# SCH_Wojcik.net
KiCad netlist of a schematic drawn in Altium Designer
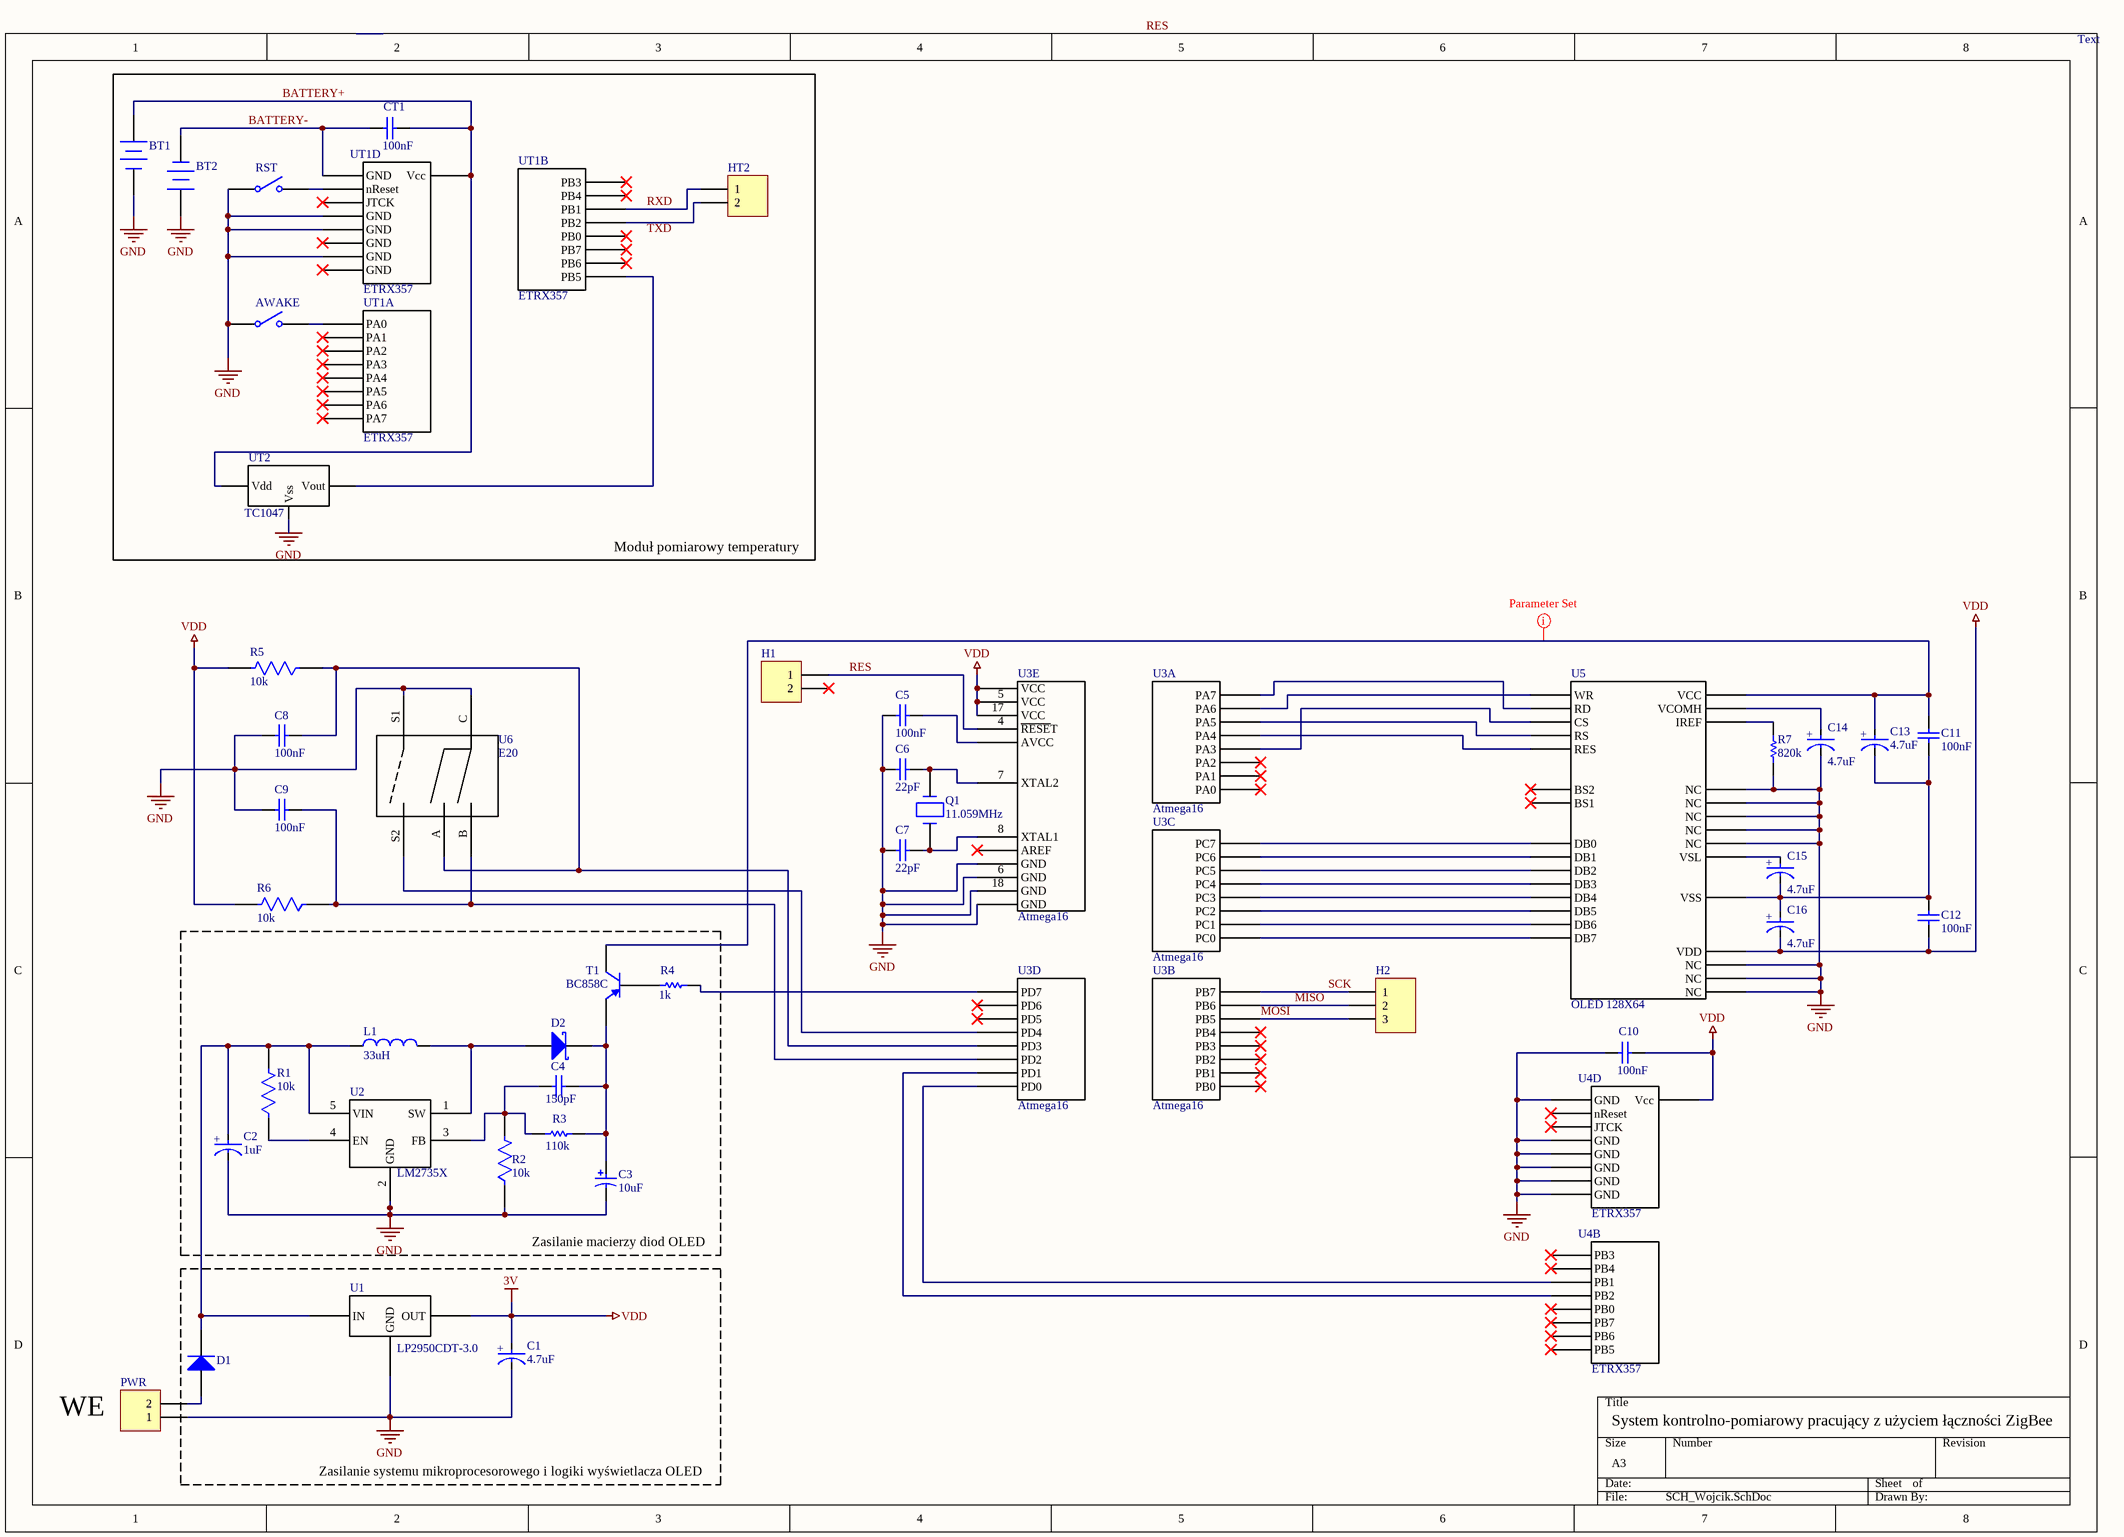
[diagram p0: SCH_Wojcik.SchDoc]

(export (version "E")
  (design (tool "Eeschema 10.0.6"))
  (components
    (comp (ref "AWAKE")
      (value "~")
      (footprint "SPST-2")
      (description "Single-Pole, Single-Throw Switch")
      (fields (field (name "PUBLISHER") "Altium Limited"))
      (libsource (lib "Miscellaneous Devices") (part "SW-SPST"))
    )
    (comp (ref "BT1")
      (value "Battery")
      (footprint "BAT-2")
      (description "Multicell Battery")
      (fields (field (name "PUBLISHER") "Altium Limited"))
      (libsource (lib "Miscellaneous Devices") (part "Battery"))
    )
    (comp (ref "BT2")
      (value "Battery")
      (footprint "BAT-2")
      (description "Multicell Battery")
      (fields (field (name "PUBLISHER") "Altium Limited"))
      (libsource (lib "Miscellaneous Devices") (part "Battery"))
    )
    (comp (ref "C1")
      (value "4.7uF")
      (footprint "FP-TAJB-MFG")
      (description "CAP TANT 4.7UF 10% 10V 1411")
      (fields
        (field (name "MANUFACTURER") "AVX Corporation")
        (field (name "MANUFACTURER PART NUMBER") "TAJB475K010RNJ")
      )
      (libsource (lib "Schlib_Wojcik_Jagienka") (part "cap4.7u"))
    )
    (comp (ref "C2")
      (value "1uF")
      (footprint "FP-TAJB-MFG")
      (description "CAP TANT 1UF 10% 35V 1411")
      (fields (field (name "TOLERANCE") "10%") (field (name "VOLTAGE") "35V"))
      (libsource (lib "Schlib_Wojcik_Jagienka") (part "1uF"))
    )
    (comp (ref "C3")
      (value "10uF")
      (footprint "CAPMP3529X21-T_V")
      (description "Standard Tantalum, 10 uF, +/- 20%, 20 V, -55 to 125 degC, 2-Pin SMD, RoHS, Tape and Reel")
      (fields (field (name "VOLTAGE") "20VDC") (field (name "MANUFACTURER") "AVX"))
      (libsource (lib "Schlib_Wojcik_Jagienka") (part "10uF"))
    )
    (comp (ref "C4")
      (value "150pF")
      (footprint "CAPC1608X90X35LL15T15")
      (fields (field (name "MANUFACTURER") "Kemet") (field (name "PART NUMBER") "C0603C151J5GAC7867"))
      (libsource (lib "Schlib_Wojcik_Jagienka") (part "150pF"))
    )
    (comp (ref "C5")
      (value "100nF")
      (footprint "CAPC1608X90X35LL10T15")
      (description "Chip Capacitor, 0.1 uF, +/- 10%, 50 V, -55 to 125 degC, 0603 (1608 Metric), RoHS, Tape and Reel")
      (fields (field (name "TOLERANCE") "10%") (field (name "VOLTAGE") "50V"))
      (libsource (lib "Schlib_Wojcik_Jagienka") (part "cap100n"))
    )
    (comp (ref "C6")
      (value "22pF")
      (footprint "CAPC1005X56X25LL10T15")
      (fields
        (field (name "PART NUMBER") "04025A220JAT2A")
        (field (name "MANUFACTURER") "AVX Interconnect / Elco")
      )
      (libsource (lib "Schlib_Wojcik_Jagienka") (part "22pF"))
    )
    (comp (ref "C7")
      (value "22pF")
      (footprint "CAPC1005X56X25LL10T15")
      (fields
        (field (name "PART NUMBER") "04025A220JAT2A")
        (field (name "MANUFACTURER") "AVX Interconnect / Elco")
      )
      (libsource (lib "Schlib_Wojcik_Jagienka") (part "22pF"))
    )
    (comp (ref "C8")
      (value "100nF")
      (footprint "CAPC1608X90X35LL10T15")
      (description "Chip Capacitor, 0.1 uF, +/- 10%, 50 V, -55 to 125 degC, 0603 (1608 Metric), RoHS, Tape and Reel")
      (fields (field (name "TOLERANCE") "10%") (field (name "VOLTAGE") "50V"))
      (libsource (lib "Schlib_Wojcik_Jagienka") (part "cap100n"))
    )
    (comp (ref "C9")
      (value "100nF")
      (footprint "CAPC1608X90X35LL10T15")
      (description "Chip Capacitor, 0.1 uF, +/- 10%, 50 V, -55 to 125 degC, 0603 (1608 Metric), RoHS, Tape and Reel")
      (fields (field (name "TOLERANCE") "10%") (field (name "VOLTAGE") "50V"))
      (libsource (lib "Schlib_Wojcik_Jagienka") (part "cap100n"))
    )
    (comp (ref "C10")
      (value "100nF")
      (footprint "CAPC1608X90X35LL10T15")
      (description "Chip Capacitor, 0.1 uF, +/- 10%, 50 V, -55 to 125 degC, 0603 (1608 Metric), RoHS, Tape and Reel")
      (fields (field (name "TOLERANCE") "10%") (field (name "VOLTAGE") "50V"))
      (libsource (lib "Schlib_Wojcik_Jagienka") (part "cap100n"))
    )
    (comp (ref "C11")
      (value "100nF")
      (footprint "CAPC1608X90X35LL10T15")
      (description "Chip Capacitor, 0.1 uF, +/- 10%, 50 V, -55 to 125 degC, 0603 (1608 Metric), RoHS, Tape and Reel")
      (fields (field (name "TOLERANCE") "10%") (field (name "VOLTAGE") "50V"))
      (libsource (lib "Schlib_Wojcik_Jagienka") (part "cap100n"))
    )
    (comp (ref "C12")
      (value "100nF")
      (footprint "CAPC1608X90X35LL10T15")
      (description "Chip Capacitor, 0.1 uF, +/- 10%, 50 V, -55 to 125 degC, 0603 (1608 Metric), RoHS, Tape and Reel")
      (fields (field (name "TOLERANCE") "10%") (field (name "VOLTAGE") "50V"))
      (libsource (lib "Schlib_Wojcik_Jagienka") (part "cap100n"))
    )
    (comp (ref "C13")
      (value "4.7uF")
      (footprint "FP-TAJB-MFG")
      (description "CAP TANT 4.7UF 10% 10V 1411")
      (fields
        (field (name "MANUFACTURER") "AVX Corporation")
        (field (name "MANUFACTURER PART NUMBER") "TAJB475K010RNJ")
      )
      (libsource (lib "Schlib_Wojcik_Jagienka") (part "cap4.7u"))
    )
    (comp (ref "C14")
      (value "4.7uF")
      (footprint "FP-TAJB-MFG")
      (description "CAP TANT 4.7UF 10% 10V 1411")
      (fields
        (field (name "MANUFACTURER") "AVX Corporation")
        (field (name "MANUFACTURER PART NUMBER") "TAJB475K010RNJ")
      )
      (libsource (lib "Schlib_Wojcik_Jagienka") (part "cap4.7u"))
    )
    (comp (ref "C15")
      (value "4.7uF")
      (footprint "FP-TAJB-MFG")
      (description "CAP TANT 4.7UF 10% 10V 1411")
      (fields
        (field (name "MANUFACTURER") "AVX Corporation")
        (field (name "MANUFACTURER PART NUMBER") "TAJB475K010RNJ")
      )
      (libsource (lib "Schlib_Wojcik_Jagienka") (part "cap4.7u"))
    )
    (comp (ref "C16")
      (value "4.7uF")
      (footprint "FP-TAJB-MFG")
      (description "CAP TANT 4.7UF 10% 10V 1411")
      (fields
        (field (name "MANUFACTURER") "AVX Corporation")
        (field (name "MANUFACTURER PART NUMBER") "TAJB475K010RNJ")
      )
      (libsource (lib "Schlib_Wojcik_Jagienka") (part "cap4.7u"))
    )
    (comp (ref "CT1")
      (value "100nF")
      (footprint "CAPC1608X90X35LL10T15")
      (description "Chip Capacitor, 0.1 uF, +/- 10%, 50 V, -55 to 125 degC, 0603 (1608 Metric), RoHS, Tape and Reel")
      (fields (field (name "TOLERANCE") "10%") (field (name "VOLTAGE") "50V"))
      (libsource (lib "Schlib_Wojcik_Jagienka") (part "cap100n"))
    )
    (comp (ref "D1")
      (value "Diode 1N5407")
      (footprint "DO-201AD")
      (description "3 Amp Medium Power Silicon Rectifier Diode")
      (fields (field (name "PUBLISHER") "Altium Limited"))
      (libsource (lib "Miscellaneous Devices") (part "Diode 1N5407"))
    )
    (comp (ref "D2")
      (value "D Schottky")
      (footprint "SMB")
      (description "Schottky Diode")
      (fields (field (name "PUBLISHER") "Altium Limited"))
      (libsource (lib "Miscellaneous Devices") (part "D Schottky"))
    )
    (comp (ref "H1")
      (value "Header 2")
      (footprint "HDR1X2")
      (description "Header, 2-Pin")
      (fields (field (name "PUBLISHER") "Altium Limited"))
      (libsource (lib "Miscellaneous Connectors") (part "Header 2"))
    )
    (comp (ref "H2")
      (value "Header 3")
      (footprint "HDR1X3")
      (description "Header, 3-Pin")
      (fields (field (name "PUBLISHER") "Altium Limited"))
      (libsource (lib "Miscellaneous Connectors") (part "Header 3"))
    )
    (comp (ref "HT2")
      (value "Header 2")
      (footprint "HDR1X2")
      (description "Header, 2-Pin")
      (fields (field (name "PUBLISHER") "Altium Limited"))
      (libsource (lib "") (part "Header 2_2"))
    )
    (comp (ref "L1")
      (value "33uH")
      (footprint "WE-PD4-L")
      (description "SMD-Power Inductor WE-PD4, L = 33.0 µH")
      (libsource (lib "Schlib_Wojcik_Jagienka") (part "CMP-0227-00804-1"))
    )
    (comp (ref "PWR")
      (value "Header 2")
      (footprint "HDR1X2")
      (description "Header, 2-Pin")
      (fields (field (name "PUBLISHER") "Altium Limited"))
      (libsource (lib "") (part "Header 2_1"))
    )
    (comp (ref "Q1")
      (value "11.059MHz")
      (footprint "XTAL_ABLS2-11.059MHZ-B4Y-T")
      (description "11.059MHz Â±30ppm Crystal 18pF 50 Ohms HC-49/US")
      (fields (field (name "DIGI-KEY_PART_NUMBER") "ABLS2-11.059MHZ-B4Y-T-ND") (field (name "MF") "Abracon"))
      (libsource (lib "ABLS2-11.059MHZ-B4Y-T") (part "ABLS2-11.059MHZ-B4Y-T"))
    )
    (comp (ref "R1")
      (value "10k")
      (footprint "FP-CRCW0402-e3-IPC_A")
      (description "RES SMD 10K OHM 1% 1/16W 0402")
      (fields (field (name "TOLERANCE") "1%"))
      (libsource (lib "Schlib_Wojcik_Jagienka") (part "10k"))
    )
    (comp (ref "R2")
      (value "10k")
      (footprint "FP-CRCW0402-e3-IPC_A")
      (description "RES SMD 10K OHM 1% 1/16W 0402")
      (fields (field (name "TOLERANCE") "1%"))
      (libsource (lib "Schlib_Wojcik_Jagienka") (part "10k"))
    )
    (comp (ref "R3")
      (value "110k")
      (footprint "RESC1005X40X25LL05T05")
      (fields (field (name "MANUFACTURER") "Vishay Dale") (field (name "PART NUMBER") "CRCW0402110KFKED"))
      (libsource (lib "Schlib_Wojcik_Jagienka") (part "110k"))
    )
    (comp (ref "R4")
      (value "1k")
      (footprint "RESC2013X50X30LL20T20")
      (fields (field (name "PART NUMBER") "CRCW08051K00FKEA") (field (name "MANUFACTURER") "Vishay Dale"))
      (libsource (lib "Schlib_Wojcik_Jagienka") (part "1k"))
    )
    (comp (ref "R5")
      (value "10k")
      (footprint "FP-CRCW0402-e3-IPC_A")
      (description "RES SMD 10K OHM 1% 1/16W 0402")
      (fields (field (name "TOLERANCE") "1%"))
      (libsource (lib "Schlib_Wojcik_Jagienka") (part "10k"))
    )
    (comp (ref "R6")
      (value "10k")
      (footprint "FP-CRCW0402-e3-IPC_A")
      (description "RES SMD 10K OHM 1% 1/16W 0402")
      (fields (field (name "TOLERANCE") "1%"))
      (libsource (lib "Schlib_Wojcik_Jagienka") (part "10k"))
    )
    (comp (ref "R7")
      (value "820k")
      (footprint "RESC1005X40X25NL05T05")
      (fields (field (name "PART NUMBER") "CRCW0402820KFKED") (field (name "MANUFACTURER") "Vishay Dale"))
      (libsource (lib "Schlib_Wojcik_Jagienka") (part "820k"))
    )
    (comp (ref "RST")
      (value "~")
      (footprint "SPST-2")
      (description "Single-Pole, Single-Throw Switch")
      (fields (field (name "PUBLISHER") "Altium Limited"))
      (libsource (lib "Miscellaneous Devices") (part "SW-SPST"))
    )
    (comp (ref "T1")
      (value "BC858C")
      (footprint "INF-SOT23_L")
      (description "PNP Silicon AF Transistor, 30 V VCEO, 100 mA IC, SOT23, Reel, Green")
      (fields (field (name "MANUFACTURER") "Infineon"))
      (libsource (lib "Schlib_Wojcik_Jagienka") (part "CMP-1177-00041-1"))
    )
    (comp (ref "U1")
      (value "LP2950CDT-3.0")
      (footprint "ON_Semi_369C_0")
      (libsource (lib "Schlib_Wojcik_Jagienka") (part "LP2950CDT-3.0"))
    )
    (comp (ref "U2")
      (value "LM2735X")
      (footprint "SOT95P280X145-5N")
      (libsource (lib "Schlib_Wojcik_Jagienka") (part "LM2735X"))
    )
    (comp (ref "U3") (value "Atmega16") (footprint "44A_L") (libsource (lib "") (part "Atmega16_4")))
    (comp (ref "U4") (value "ETRX357") (footprint "ETRX357") (libsource (lib "") (part "ETRX357_3")))
    (comp (ref "U5") (value "OLED 128X64") (libsource (lib "Schlib_Wojcik_Jagienka") (part "OLED")))
    (comp (ref "U6")
      (value "E20")
      (footprint "Encoder")
      (libsource (lib "Schlib_Wojcik_Jagienka") (part "E20"))
    )
    (comp (ref "UT1") (value "ETRX357") (footprint "ETRX357") (libsource (lib "") (part "ETRX357_4")))
    (comp (ref "UT2")
      (value "TC1047")
      (footprint "SOT-23")
      (libsource (lib "Schlib_Wojcik_Jagienka") (part "TC1047"))
    )
  )
  (nets
    (net (code "1") (name "/BATTERY+") (class "Default")
      (node (ref "BT1") (pin "1") (pinfunction "+_1") (pintype "passive"))
      (node (ref "CT1") (pin "2") (pinfunction "2_2") (pintype "passive"))
      (node (ref "UT1") (pin "32") (pinfunction "Vcc_32") (pintype "passive"))
      (node (ref "UT2") (pin "1") (pinfunction "Vdd_1") (pintype "passive"))
    )
    (net (code "2") (name "/BATTERY-") (class "Default")
      (node (ref "BT2") (pin "2") (pinfunction "-_2") (pintype "passive"))
      (node (ref "CT1") (pin "1") (pinfunction "1_1") (pintype "passive"))
      (node (ref "UT1") (pin "1") (pinfunction "GND_1") (pintype "passive"))
    )
    (net (code "3") (name "/MISO") (class "Default")
      (node (ref "H2") (pin "2") (pinfunction "2_2") (pintype "passive"))
      (node (ref "U3") (pin "2") (pinfunction "PB6_2") (pintype "passive"))
    )
    (net (code "4") (name "/MOSI") (class "Default")
      (node (ref "H2") (pin "3") (pinfunction "3_3") (pintype "passive"))
      (node (ref "U3") (pin "1") (pinfunction "PB5_1") (pintype "passive"))
    )
    (net (code "5") (name "/RES") (class "Default")
      (node (ref "H1") (pin "1") (pinfunction "1_1") (pintype "passive"))
      (node (ref "U3") (pin "4") (pinfunction "~{RESE}T_4") (pintype "passive"))
    )
    (net (code "6") (name "/RXD") (class "Default")
      (node (ref "HT2") (pin "1") (pinfunction "1_1") (pintype "passive"))
      (node (ref "UT1") (pin "17") (pinfunction "PB1_17") (pintype "passive"))
    )
    (net (code "7") (name "/SCK") (class "Default")
      (node (ref "H2") (pin "1") (pinfunction "1_1") (pintype "passive"))
      (node (ref "U3") (pin "3") (pinfunction "PB7_3") (pintype "passive"))
    )
    (net (code "9") (name "3V") (class "Default")
      (node (ref "C1") (pin "2") (pinfunction "A_2") (pintype "passive"))
      (node (ref "C10") (pin "2") (pinfunction "2_2") (pintype "passive"))
      (node (ref "C12") (pin "1") (pinfunction "1_1") (pintype "passive"))
      (node (ref "C16") (pin "1") (pinfunction "C_1") (pintype "passive"))
      (node (ref "R5") (pin "2") (pinfunction "2_2") (pintype "passive"))
      (node (ref "R6") (pin "2") (pinfunction "2_2") (pintype "passive"))
      (node (ref "U1") (pin "3") (pinfunction "OUT_3") (pintype "passive"))
      (node (ref "U3") (pin "17") (pinfunction "VCC_17") (pintype "passive"))
      (node (ref "U3") (pin "38") (pinfunction "VCC_38") (pintype "passive"))
      (node (ref "U3") (pin "5") (pinfunction "VCC_5") (pintype "passive"))
      (node (ref "U4") (pin "32") (pinfunction "Vcc_32") (pintype "passive"))
      (node (ref "U5") (pin "21") (pinfunction "VDD_21") (pintype "passive"))
    )
    (net (code "10") (name "GND") (class "Default")
      (node (ref "AWAKE") (pin "1") (pinfunction "COMMON_1") (pintype "passive"))
      (node (ref "BT1") (pin "2") (pinfunction "-_2") (pintype "passive"))
      (node (ref "BT2") (pin "1") (pinfunction "+_1") (pintype "passive"))
      (node (ref "C1") (pin "1") (pinfunction "C_1") (pintype "passive"))
      (node (ref "C10") (pin "1") (pinfunction "1_1") (pintype "passive"))
      (node (ref "C14") (pin "1") (pinfunction "C_1") (pintype "passive"))
      (node (ref "C2") (pin "1") (pinfunction "C_1") (pintype "passive"))
      (node (ref "C3") (pin "2") (pinfunction "2_2") (pintype "passive"))
      (node (ref "C5") (pin "1") (pinfunction "1_1") (pintype "passive"))
      (node (ref "C6") (pin "1") (pinfunction "1_1") (pintype "passive"))
      (node (ref "C7") (pin "1") (pinfunction "1_1") (pintype "passive"))
      (node (ref "C8") (pin "1") (pinfunction "1_1") (pintype "passive"))
      (node (ref "C9") (pin "1") (pinfunction "1_1") (pintype "passive"))
      (node (ref "PWR") (pin "1") (pinfunction "1_1") (pintype "passive"))
      (node (ref "R2") (pin "1") (pinfunction "1_1") (pintype "passive"))
      (node (ref "R7") (pin "1") (pinfunction "1_1") (pintype "passive"))
      (node (ref "RST") (pin "1") (pinfunction "COMMON_1") (pintype "passive"))
      (node (ref "U1") (pin "2") (pinfunction "GND_2") (pintype "passive"))
      (node (ref "U2") (pin "2") (pinfunction "GND_2") (pintype "passive"))
      (node (ref "U3") (pin "18") (pinfunction "GND_18") (pintype "passive"))
      (node (ref "U3") (pin "28") (pinfunction "GND_28") (pintype "passive"))
      (node (ref "U3") (pin "39") (pinfunction "GND_39") (pintype "passive"))
      (node (ref "U3") (pin "6") (pinfunction "GND_6") (pintype "passive"))
      (node (ref "U4") (pin "1") (pinfunction "GND_1") (pintype "passive"))
      (node (ref "U4") (pin "13") (pinfunction "GND_13") (pintype "passive"))
      (node (ref "U4") (pin "19") (pinfunction "GND_19") (pintype "passive"))
      (node (ref "U4") (pin "20") (pinfunction "GND_20") (pintype "passive"))
      (node (ref "U4") (pin "31") (pinfunction "GND_31") (pintype "passive"))
      (node (ref "U4") (pin "33") (pinfunction "GND_33") (pintype "passive"))
      (node (ref "U5") (pin "18") (pinfunction "NC_18") (pintype "passive"))
      (node (ref "U5") (pin "22") (pinfunction "NC_22") (pintype "passive"))
      (node (ref "U5") (pin "23") (pinfunction "NC_23") (pintype "passive"))
      (node (ref "U5") (pin "24") (pinfunction "NC_24") (pintype "passive"))
      (node (ref "U5") (pin "25") (pinfunction "NC_25") (pintype "passive"))
      (node (ref "U5") (pin "26") (pinfunction "NC_26") (pintype "passive"))
      (node (ref "U5") (pin "27") (pinfunction "NC_27") (pintype "passive"))
      (node (ref "U5") (pin "28") (pinfunction "NC_28") (pintype "passive"))
      (node (ref "U6") (pin "C") (pintype "passive"))
      (node (ref "U6") (pin "S1") (pintype "passive"))
      (node (ref "UT1") (pin "13") (pinfunction "GND_13") (pintype "passive"))
      (node (ref "UT1") (pin "20") (pinfunction "GND_20") (pintype "passive"))
      (node (ref "UT1") (pin "33") (pinfunction "GND_33") (pintype "passive"))
      (node (ref "UT2") (pin "3") (pinfunction "Vss_3") (pintype "passive"))
    )
    (net (code "11") (name "Net-(AWAKE-NO)") (class "Default")
      (node (ref "AWAKE") (pin "2") (pinfunction "NO_2") (pintype "passive"))
      (node (ref "UT1") (pin "9") (pinfunction "PA0_9") (pintype "passive"))
    )
    (net (code "12") (name "Net-(C2-A)") (class "Default")
      (node (ref "C2") (pin "2") (pinfunction "A_2") (pintype "passive"))
      (node (ref "D1") (pin "2") (pinfunction "K_2") (pintype "passive"))
      (node (ref "L1") (pin "1") (pinfunction "1_1") (pintype "passive"))
      (node (ref "R1") (pin "2") (pinfunction "2_2") (pintype "passive"))
      (node (ref "U1") (pin "1") (pinfunction "IN_1") (pintype "passive"))
      (node (ref "U2") (pin "5") (pinfunction "VIN_5") (pintype "passive"))
    )
    (net (code "13") (name "Net-(C13-A)") (class "Default")
      (node (ref "C11") (pin "2") (pinfunction "2_2") (pintype "passive"))
      (node (ref "C13") (pin "2") (pinfunction "A_2") (pintype "passive"))
      (node (ref "T1") (pin "3") (pinfunction "C_3") (pintype "passive"))
      (node (ref "U5") (pin "2") (pinfunction "VCC_2") (pintype "passive"))
    )
    (net (code "14") (name "Net-(C13-C)") (class "Default")
      (node (ref "C11") (pin "1") (pinfunction "1_1") (pintype "passive"))
      (node (ref "C12") (pin "2") (pinfunction "2_2") (pintype "passive"))
      (node (ref "C13") (pin "1") (pinfunction "C_1") (pintype "passive"))
      (node (ref "C15") (pin "1") (pinfunction "C_1") (pintype "passive"))
      (node (ref "C16") (pin "2") (pinfunction "A_2") (pintype "passive"))
      (node (ref "U5") (pin "29") (pinfunction "VSS_29") (pintype "passive"))
    )
    (net (code "15") (name "Net-(C14-A)") (class "Default")
      (node (ref "C14") (pin "2") (pinfunction "A_2") (pintype "passive"))
      (node (ref "U5") (pin "3") (pinfunction "VCOMH_3") (pintype "passive"))
    )
    (net (code "16") (name "Net-(C15-A)") (class "Default")
      (node (ref "C15") (pin "2") (pinfunction "A_2") (pintype "passive"))
      (node (ref "U5") (pin "30") (pinfunction "VSL_30") (pintype "passive"))
    )
    (net (code "17") (name "Net-(D1-A)") (class "Default")
      (node (ref "D1") (pin "1") (pinfunction "A_1") (pintype "passive"))
      (node (ref "PWR") (pin "2") (pinfunction "2_2") (pintype "passive"))
    )
    (net (code "18") (name "Net-(D2-A)") (class "Default")
      (node (ref "D2") (pin "1") (pinfunction "A_1") (pintype "passive"))
      (node (ref "L1") (pin "2") (pinfunction "2_2") (pintype "passive"))
      (node (ref "U2") (pin "1") (pinfunction "SW_1") (pintype "passive"))
    )
    (net (code "19") (name "Net-(D2-K)") (class "Default")
      (node (ref "C3") (pin "1") (pinfunction "1_1") (pintype "passive"))
      (node (ref "C4") (pin "2") (pinfunction "2_2") (pintype "passive"))
      (node (ref "D2") (pin "2") (pinfunction "K_2") (pintype "passive"))
      (node (ref "R3") (pin "2") (pinfunction "2_2") (pintype "passive"))
      (node (ref "T1") (pin "2") (pinfunction "E_2") (pintype "passive"))
    )
    (net (code "20") (name "Net-(RST-NO)") (class "Default")
      (node (ref "RST") (pin "2") (pinfunction "NO_2") (pintype "passive"))
      (node (ref "UT1") (pin "7") (pinfunction "nReset_7") (pintype "passive"))
    )
    (net (code "21") (name "Net-(T1-B)") (class "Default")
      (node (ref "R4") (pin "1") (pinfunction "1_1") (pintype "passive"))
      (node (ref "T1") (pin "1") (pinfunction "B_1") (pintype "passive"))
    )
    (net (code "22") (name "Net-(U2-EN)") (class "Default")
      (node (ref "R1") (pin "1") (pinfunction "1_1") (pintype "passive"))
      (node (ref "U2") (pin "4") (pinfunction "EN_4") (pintype "passive"))
    )
    (net (code "23") (name "Net-(U2-FB)") (class "Default")
      (node (ref "C4") (pin "1") (pinfunction "1_1") (pintype "passive"))
      (node (ref "R2") (pin "2") (pinfunction "2_2") (pintype "passive"))
      (node (ref "R3") (pin "1") (pinfunction "1_1") (pintype "passive"))
      (node (ref "U2") (pin "3") (pinfunction "FB_3") (pintype "passive"))
    )
    (net (code "24") (name "Net-(U3A-PA3)") (class "Default")
      (node (ref "U3") (pin "34") (pinfunction "PA3_34") (pintype "passive"))
      (node (ref "U5") (pin "15") (pinfunction "CS_15") (pintype "passive"))
    )
    (net (code "25") (name "Net-(U3A-PA4)") (class "Default")
      (node (ref "U3") (pin "33") (pinfunction "PA4_33") (pintype "passive"))
      (node (ref "U5") (pin "26") (pinfunction "RES_26") (pintype "passive"))
    )
    (net (code "26") (name "Net-(U3A-PA5)") (class "Default")
      (node (ref "U3") (pin "32") (pinfunction "PA5_32") (pintype "passive"))
      (node (ref "U5") (pin "17") (pinfunction "RS_17") (pintype "passive"))
    )
    (net (code "27") (name "Net-(U3A-PA6)") (class "Default")
      (node (ref "U3") (pin "31") (pinfunction "PA6_31") (pintype "passive"))
      (node (ref "U5") (pin "14") (pinfunction "WR_14") (pintype "passive"))
    )
    (net (code "28") (name "Net-(U3A-PA7)") (class "Default")
      (node (ref "U3") (pin "30") (pinfunction "PA7_30") (pintype "passive"))
      (node (ref "U5") (pin "13") (pinfunction "RD_13") (pintype "passive"))
    )
    (net (code "29") (name "Net-(U3C-PC0)") (class "Default")
      (node (ref "U3") (pin "19") (pinfunction "PC0_19") (pintype "passive"))
      (node (ref "U5") (pin "5") (pinfunction "DB7_5") (pintype "passive"))
    )
    (net (code "30") (name "Net-(U3C-PC1)") (class "Default")
      (node (ref "U3") (pin "20") (pinfunction "PC1_20") (pintype "passive"))
      (node (ref "U5") (pin "6") (pinfunction "DB6_6") (pintype "passive"))
    )
    (net (code "31") (name "Net-(U3C-PC2)") (class "Default")
      (node (ref "U3") (pin "21") (pinfunction "PC2_21") (pintype "passive"))
      (node (ref "U5") (pin "7") (pinfunction "DB5_7") (pintype "passive"))
    )
    (net (code "32") (name "Net-(U3C-PC3)") (class "Default")
      (node (ref "U3") (pin "22") (pinfunction "PC3_22") (pintype "passive"))
      (node (ref "U5") (pin "8") (pinfunction "DB4_8") (pintype "passive"))
    )
    (net (code "33") (name "Net-(U3C-PC4)") (class "Default")
      (node (ref "U3") (pin "23") (pinfunction "PC4_23") (pintype "passive"))
      (node (ref "U5") (pin "9") (pinfunction "DB3_9") (pintype "passive"))
    )
    (net (code "34") (name "Net-(U3C-PC5)") (class "Default")
      (node (ref "U3") (pin "24") (pinfunction "PC5_24") (pintype "passive"))
      (node (ref "U5") (pin "10") (pinfunction "DB2_10") (pintype "passive"))
    )
    (net (code "35") (name "Net-(U3C-PC6)") (class "Default")
      (node (ref "U3") (pin "25") (pinfunction "PC6_25") (pintype "passive"))
      (node (ref "U5") (pin "11") (pinfunction "DB1_11") (pintype "passive"))
    )
    (net (code "36") (name "Net-(U3C-PC7)") (class "Default")
      (node (ref "U3") (pin "26") (pinfunction "PC7_26") (pintype "passive"))
      (node (ref "U5") (pin "12") (pinfunction "DB0_12") (pintype "passive"))
    )
    (net (code "37") (name "Net-(U3D-PD0)") (class "Default")
      (node (ref "U3") (pin "9") (pinfunction "PD0_9") (pintype "passive"))
      (node (ref "U4") (pin "17") (pinfunction "PB1_17") (pintype "passive"))
    )
    (net (code "38") (name "Net-(U3D-PD1)") (class "Default")
      (node (ref "U3") (pin "10") (pinfunction "PD1_10") (pintype "passive"))
      (node (ref "U4") (pin "18") (pinfunction "PB2_18") (pintype "passive"))
    )
    (net (code "39") (name "Net-(U3D-PD2)") (class "Default")
      (node (ref "C9") (pin "2") (pinfunction "2_2") (pintype "passive"))
      (node (ref "R6") (pin "1") (pinfunction "1_1") (pintype "passive"))
      (node (ref "U3") (pin "11") (pinfunction "PD2_11") (pintype "passive"))
      (node (ref "U6") (pin "B") (pintype "passive"))
    )
    (net (code "40") (name "Net-(U3D-PD3)") (class "Default")
      (node (ref "C8") (pin "2") (pinfunction "2_2") (pintype "passive"))
      (node (ref "R5") (pin "1") (pinfunction "1_1") (pintype "passive"))
      (node (ref "U3") (pin "17") (pinfunction "PD3_17") (pintype "passive"))
      (node (ref "U6") (pin "A") (pintype "passive"))
    )
    (net (code "41") (name "Net-(U3D-PD4)") (class "Default")
      (node (ref "U3") (pin "12") (pinfunction "PD4_12") (pintype "passive"))
      (node (ref "U6") (pin "S2") (pintype "passive"))
    )
    (net (code "42") (name "Net-(U3D-PD7)") (class "Default")
      (node (ref "R4") (pin "2") (pinfunction "2_2") (pintype "passive"))
      (node (ref "U3") (pin "16") (pinfunction "PD7_16") (pintype "passive"))
    )
    (net (code "43") (name "Net-(U3E-AVCC)") (class "Default")
      (node (ref "C5") (pin "2") (pinfunction "2_2") (pintype "passive"))
      (node (ref "U3") (pin "27") (pinfunction "AVCC_27") (pintype "passive"))
    )
    (net (code "44") (name "Net-(U3E-XTAL1)") (class "Default")
      (node (ref "C7") (pin "2") (pinfunction "2_2") (pintype "passive"))
      (node (ref "Q1") (pin "1") (pinfunction "1_1") (pintype "passive"))
      (node (ref "U3") (pin "8") (pinfunction "XTAL1_8") (pintype "passive"))
    )
    (net (code "45") (name "Net-(U3E-XTAL2)") (class "Default")
      (node (ref "C6") (pin "2") (pinfunction "2_2") (pintype "passive"))
      (node (ref "Q1") (pin "2") (pinfunction "2_2") (pintype "passive"))
      (node (ref "U3") (pin "7") (pinfunction "XTAL2_7") (pintype "passive"))
    )
    (net (code "46") (name "Net-(U5-IREF)") (class "Default")
      (node (ref "R7") (pin "2") (pinfunction "2_2") (pintype "passive"))
      (node (ref "U5") (pin "4") (pinfunction "IREF_4") (pintype "passive"))
    )
    (net (code "47") (name "Net-(UT1B-PB2)") (class "Default")
      (node (ref "HT2") (pin "2") (pinfunction "2_2") (pintype "passive"))
      (node (ref "UT1") (pin "18") (pinfunction "PB2_18") (pintype "passive"))
    )
    (net (code "48") (name "Net-(UT1B-PB5)") (class "Default")
      (node (ref "UT1") (pin "30") (pinfunction "PB5_30") (pintype "passive"))
      (node (ref "UT2") (pin "2") (pinfunction "Vout_2") (pintype "passive"))
    )
    (net (code "49") (name "unconnected-(H1-Pad2)") (class "Default")
      (node (ref "H1") (pin "2") (pinfunction "2_2") (pintype "passive+no_connect"))
    )
    (net (code "50") (name "unconnected-(U3A-PA0-Pad37)") (class "Default")
      (node (ref "U3") (pin "37") (pinfunction "PA0_37") (pintype "passive+no_connect"))
    )
    (net (code "51") (name "unconnected-(U3A-PA1-Pad36)") (class "Default")
      (node (ref "U3") (pin "36") (pinfunction "PA1_36") (pintype "passive+no_connect"))
    )
    (net (code "52") (name "unconnected-(U3A-PA2-Pad35)") (class "Default")
      (node (ref "U3") (pin "35") (pinfunction "PA2_35") (pintype "passive+no_connect"))
    )
    (net (code "53") (name "unconnected-(U3B-PB0-Pad40)") (class "Default")
      (node (ref "U3") (pin "40") (pinfunction "PB0_40") (pintype "passive+no_connect"))
    )
    (net (code "54") (name "unconnected-(U3B-PB1-Pad41)") (class "Default")
      (node (ref "U3") (pin "41") (pinfunction "PB1_41") (pintype "passive+no_connect"))
    )
    (net (code "55") (name "unconnected-(U3B-PB2-Pad42)") (class "Default")
      (node (ref "U3") (pin "42") (pinfunction "PB2_42") (pintype "passive+no_connect"))
    )
    (net (code "56") (name "unconnected-(U3B-PB3-Pad43)") (class "Default")
      (node (ref "U3") (pin "43") (pinfunction "PB3_43") (pintype "passive+no_connect"))
    )
    (net (code "57") (name "unconnected-(U3B-PB4-Pad44)") (class "Default")
      (node (ref "U3") (pin "44") (pinfunction "PB4_44") (pintype "passive+no_connect"))
    )
    (net (code "58") (name "unconnected-(U3D-PD5-Pad14)") (class "Default")
      (node (ref "U3") (pin "14") (pinfunction "PD5_14") (pintype "passive+no_connect"))
    )
    (net (code "59") (name "unconnected-(U3D-PD6-Pad15)") (class "Default")
      (node (ref "U3") (pin "15") (pinfunction "PD6_15") (pintype "passive+no_connect"))
    )
    (net (code "60") (name "unconnected-(U3E-AREF-Pad29)") (class "Default")
      (node (ref "U3") (pin "29") (pinfunction "AREF_29") (pintype "passive+no_connect"))
    )
    (net (code "61") (name "unconnected-(U4B-PB0-Pad25)") (class "Default")
      (node (ref "U4") (pin "25") (pinfunction "PB0_25") (pintype "passive+no_connect"))
    )
    (net (code "62") (name "unconnected-(U4B-PB3-Pad6)") (class "Default")
      (node (ref "U4") (pin "6") (pinfunction "PB3_6") (pintype "passive+no_connect"))
    )
    (net (code "63") (name "unconnected-(U4B-PB4-Pad8)") (class "Default")
      (node (ref "U4") (pin "8") (pinfunction "PB4_8") (pintype "passive+no_connect"))
    )
    (net (code "64") (name "unconnected-(U4B-PB5-Pad30)") (class "Default")
      (node (ref "U4") (pin "30") (pinfunction "PB5_30") (pintype "passive+no_connect"))
    )
    (net (code "65") (name "unconnected-(U4B-PB6-Pad29)") (class "Default")
      (node (ref "U4") (pin "29") (pinfunction "PB6_29") (pintype "passive+no_connect"))
    )
    (net (code "66") (name "unconnected-(U4B-PB7-Pad28)") (class "Default")
      (node (ref "U4") (pin "28") (pinfunction "PB7_28") (pintype "passive+no_connect"))
    )
    (net (code "67") (name "unconnected-(U4D-JTCK-Pad21)") (class "Default")
      (node (ref "U4") (pin "21") (pinfunction "JTCK_21") (pintype "passive+no_connect"))
    )
    (net (code "68") (name "unconnected-(U4D-nReset-Pad7)") (class "Default")
      (node (ref "U4") (pin "7") (pinfunction "nReset_7") (pintype "passive+no_connect"))
    )
    (net (code "69") (name "unconnected-(U5-BS1-Pad20)") (class "Default")
      (node (ref "U5") (pin "20") (pinfunction "BS1_20") (pintype "passive+no_connect"))
    )
    (net (code "70") (name "unconnected-(U5-BS2-Pad19)") (class "Default")
      (node (ref "U5") (pin "19") (pinfunction "BS2_19") (pintype "passive+no_connect"))
    )
    (net (code "71") (name "unconnected-(UT1A-PA1-Pad10)") (class "Default")
      (node (ref "UT1") (pin "10") (pinfunction "PA1_10") (pintype "passive+no_connect"))
    )
    (net (code "72") (name "unconnected-(UT1A-PA2-Pad11)") (class "Default")
      (node (ref "UT1") (pin "11") (pinfunction "PA2_11") (pintype "passive+no_connect"))
    )
    (net (code "73") (name "unconnected-(UT1A-PA3-Pad12)") (class "Default")
      (node (ref "UT1") (pin "12") (pinfunction "PA3_12") (pintype "passive+no_connect"))
    )
    (net (code "74") (name "unconnected-(UT1A-PA4-Pad14)") (class "Default")
      (node (ref "UT1") (pin "14") (pinfunction "PA4_14") (pintype "passive+no_connect"))
    )
    (net (code "75") (name "unconnected-(UT1A-PA5-Pad15)") (class "Default")
      (node (ref "UT1") (pin "15") (pinfunction "PA5_15") (pintype "passive+no_connect"))
    )
    (net (code "76") (name "unconnected-(UT1A-PA6-Pad16)") (class "Default")
      (node (ref "UT1") (pin "16") (pinfunction "PA6_16") (pintype "passive+no_connect"))
    )
    (net (code "77") (name "unconnected-(UT1A-PA7-Pad5)") (class "Default")
      (node (ref "UT1") (pin "5") (pinfunction "PA7_5") (pintype "passive+no_connect"))
    )
    (net (code "78") (name "unconnected-(UT1B-PB0-Pad25)") (class "Default")
      (node (ref "UT1") (pin "25") (pinfunction "PB0_25") (pintype "passive+no_connect"))
    )
    (net (code "79") (name "unconnected-(UT1B-PB3-Pad6)") (class "Default")
      (node (ref "UT1") (pin "6") (pinfunction "PB3_6") (pintype "passive+no_connect"))
    )
    (net (code "80") (name "unconnected-(UT1B-PB4-Pad8)") (class "Default")
      (node (ref "UT1") (pin "8") (pinfunction "PB4_8") (pintype "passive+no_connect"))
    )
    (net (code "81") (name "unconnected-(UT1B-PB6-Pad29)") (class "Default")
      (node (ref "UT1") (pin "29") (pinfunction "PB6_29") (pintype "passive+no_connect"))
    )
    (net (code "82") (name "unconnected-(UT1B-PB7-Pad28)") (class "Default")
      (node (ref "UT1") (pin "28") (pinfunction "PB7_28") (pintype "passive+no_connect"))
    )
    (net (code "83") (name "unconnected-(UT1D-GND-Pad19)") (class "Default")
      (node (ref "UT1") (pin "19") (pinfunction "GND_19") (pintype "passive+no_connect"))
    )
    (net (code "84") (name "unconnected-(UT1D-GND-Pad31)") (class "Default")
      (node (ref "UT1") (pin "31") (pinfunction "GND_31") (pintype "passive+no_connect"))
    )
    (net (code "85") (name "unconnected-(UT1D-JTCK-Pad21)") (class "Default")
      (node (ref "UT1") (pin "21") (pinfunction "JTCK_21") (pintype "passive+no_connect"))
    )
  )
)
